# power.net
KiCad netlist of a schematic drawn in Altium Designer
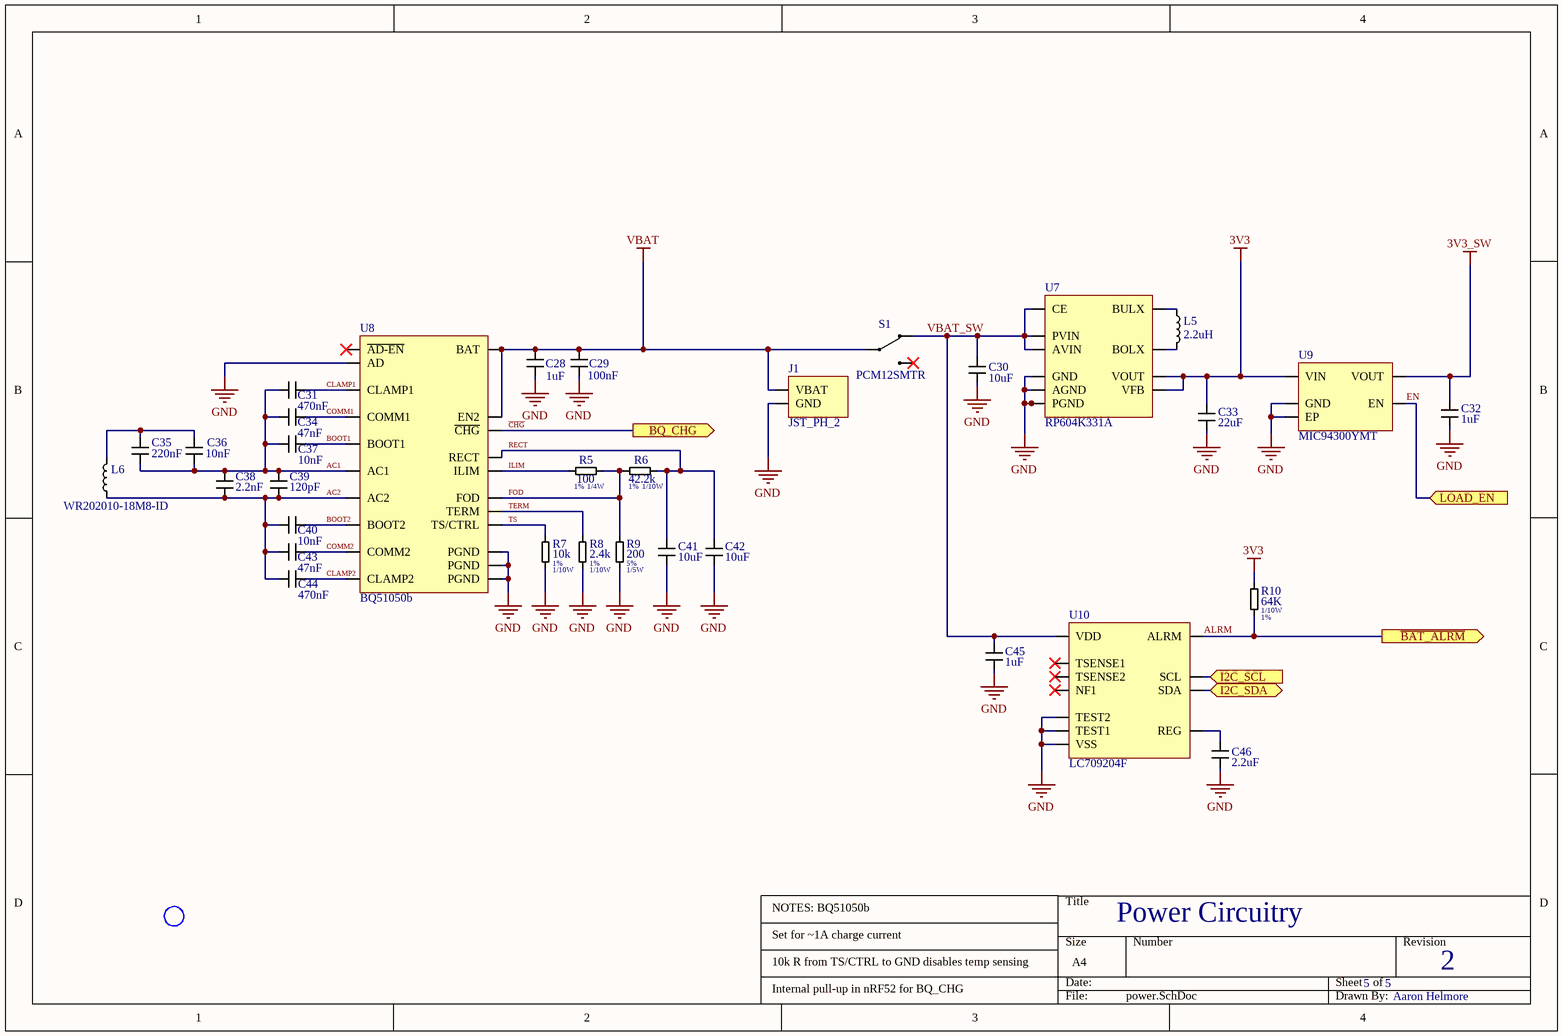
[diagram p0: power.SchDoc]

(export (version "E")
  (design (tool "Eeschema 10.0.6"))
  (components
    (comp (ref "C28")
      (value "1uF")
      (footprint "CAP_0402")
      (fields (field (name "VOLTAGE") "25V"))
      (libsource (lib "thesis_schem_lib") (part "Capacitor"))
    )
    (comp (ref "C29")
      (value "100nF")
      (footprint "CAP_0402")
      (fields (field (name "VOLTAGE") "25V"))
      (libsource (lib "thesis_schem_lib") (part "Capacitor"))
    )
    (comp (ref "C30")
      (value "10uF")
      (footprint "CAP_0603")
      (fields (field (name "VOLTAGE") "25V"))
      (libsource (lib "thesis_schem_lib") (part "Capacitor"))
    )
    (comp (ref "C31")
      (value "470nF")
      (footprint "CAP_0603")
      (fields (field (name "VOLTAGE") "25V"))
      (libsource (lib "thesis_schem_lib") (part "Capacitor"))
    )
    (comp (ref "C32")
      (value "1uF")
      (footprint "CAP_0402")
      (fields (field (name "VOLTAGE") "25V"))
      (libsource (lib "thesis_schem_lib") (part "Capacitor"))
    )
    (comp (ref "C33")
      (value "22uF")
      (footprint "CAP_0603")
      (fields (field (name "VOLTAGE") "10V"))
      (libsource (lib "thesis_schem_lib") (part "Capacitor"))
    )
    (comp (ref "C34")
      (value "47nF")
      (footprint "CAP_0402")
      (fields (field (name "VOLTAGE") "25V"))
      (libsource (lib "thesis_schem_lib") (part "Capacitor"))
    )
    (comp (ref "C35")
      (value "220nF")
      (footprint "CAP_0402")
      (fields (field (name "VOLTAGE") "25V"))
      (libsource (lib "thesis_schem_lib") (part "Capacitor"))
    )
    (comp (ref "C36")
      (value "10nF")
      (footprint "CAP_0402")
      (fields (field (name "VOLTAGE") "25V"))
      (libsource (lib "thesis_schem_lib") (part "Capacitor"))
    )
    (comp (ref "C37")
      (value "10nF")
      (footprint "CAP_0402")
      (fields (field (name "VOLTAGE") "25V"))
      (libsource (lib "") (part "Capacitor_1"))
    )
    (comp (ref "C38")
      (value "2.2nF")
      (footprint "CAP_0402")
      (fields (field (name "VOLTAGE") "50V"))
      (libsource (lib "thesis_schem_lib") (part "Capacitor"))
    )
    (comp (ref "C39")
      (value "120pF")
      (footprint "CAP_0402")
      (fields (field (name "VOLTAGE") "50V"))
      (libsource (lib "thesis_schem_lib") (part "Capacitor"))
    )
    (comp (ref "C40")
      (value "10nF")
      (footprint "CAP_0402")
      (fields (field (name "VOLTAGE") "25V"))
      (libsource (lib "thesis_schem_lib") (part "Capacitor"))
    )
    (comp (ref "C41")
      (value "10uF")
      (footprint "CAP_0603")
      (fields (field (name "VOLTAGE") "25V"))
      (libsource (lib "thesis_schem_lib") (part "Capacitor"))
    )
    (comp (ref "C42")
      (value "10uF")
      (footprint "CAP_0603")
      (fields (field (name "VOLTAGE") "25V"))
      (libsource (lib "thesis_schem_lib") (part "Capacitor"))
    )
    (comp (ref "C43")
      (value "47nF")
      (footprint "CAP_0402")
      (fields (field (name "VOLTAGE") "25V"))
      (libsource (lib "thesis_schem_lib") (part "Capacitor"))
    )
    (comp (ref "C44")
      (value "470nF")
      (footprint "CAP_0603")
      (fields (field (name "VOLTAGE") "25V"))
      (libsource (lib "thesis_schem_lib") (part "Capacitor"))
    )
    (comp (ref "C45")
      (value "1uF")
      (footprint "CAP_0402")
      (fields (field (name "VOLTAGE") "25V"))
      (libsource (lib "thesis_schem_lib") (part "Capacitor"))
    )
    (comp (ref "C46")
      (value "2.2uF")
      (footprint "CAP_0603")
      (fields (field (name "VOLTAGE") "25V"))
      (libsource (lib "thesis_schem_lib") (part "Capacitor"))
    )
    (comp (ref "J1")
      (value "JST_PH_2")
      (footprint "JST PH2 SMT")
      (description "JST PH series connector with 2 pins 1 row")
      (libsource (lib "thesis_schem_lib") (part "JST_PH_2"))
    )
    (comp (ref "L5")
      (value "2.2uH")
      (footprint "LQM2MPNxxxx")
      (libsource (lib "thesis_schem_lib") (part "Inductor"))
    )
    (comp (ref "L6")
      (value "WR202010-18M8-ID")
      (footprint "WR202010")
      (libsource (lib "thesis_schem_lib") (part "Inductor"))
    )
    (comp (ref "R5")
      (value "100")
      (footprint "RES_0402")
      (fields (field (name "TOLERANCE") "1%") (field (name "WATTAGE") "1/4W"))
      (libsource (lib "") (part "R_Small_1"))
    )
    (comp (ref "R6")
      (value "42.2k")
      (footprint "RES_0402")
      (fields (field (name "TOLERANCE") "1%") (field (name "WATTAGE") "1/10W"))
      (libsource (lib "") (part "R_Small_1"))
    )
    (comp (ref "R7")
      (value "10k")
      (footprint "RES_0402")
      (fields (field (name "TOLERANCE") "1%") (field (name "WATTAGE") "1/10W"))
      (libsource (lib "thesis_schem_lib") (part "R_Small"))
    )
    (comp (ref "R8")
      (value "2.4k")
      (footprint "RES_0402")
      (fields (field (name "TOLERANCE") "1%") (field (name "WATTAGE") "1/10W"))
      (libsource (lib "thesis_schem_lib") (part "R_Small"))
    )
    (comp (ref "R9")
      (value "200")
      (footprint "RES_0402")
      (fields (field (name "TOLERANCE") "5%") (field (name "WATTAGE") "1/5W"))
      (libsource (lib "thesis_schem_lib") (part "R_Small"))
    )
    (comp (ref "R10")
      (value "64K")
      (footprint "RES_0402")
      (fields (field (name "WATTAGE") "1/10W") (field (name "TOLERANCE") "1%"))
      (libsource (lib "thesis_schem_lib") (part "R_Small"))
    )
    (comp (ref "RXCOIL1")
      (value "RXCOIL_MISC")
      (footprint "RX_COIL_MISC")
      (libsource (lib "thesis_schem_lib") (part "RXCOIL_MISC"))
    )
    (comp (ref "S1")
      (value "PCM12SMTR")
      (footprint "PCM12SMTR")
      (description "CK Switches 300mA 6VDC SMT right-angle slide switch")
      (libsource (lib "thesis_schem_lib") (part "PCM12SMTR"))
    )
    (comp (ref "U7")
      (value "RP604K331A")
      (footprint "UDFN-12")
      (description "Nisshinbo Ultra-low quiescent current, 300mA, Buck-Boost DC/DC converter")
      (libsource (lib "thesis_schem_lib") (part "RP604K331A"))
    )
    (comp (ref "U8")
      (value "BQ51050b")
      (footprint "BQ51050b-VQFN")
      (description "Single stage wireless power receiver and Li-Ion/Li-Pol battery charger. Qi compatible")
      (libsource (lib "thesis_schem_lib") (part "BQ51050b"))
    )
    (comp (ref "U9")
      (value "MIC94300YMT")
      (footprint "MIC94300YMT")
      (description "200mA load switch")
      (libsource (lib "thesis_schem_lib") (part "MIC94300YMT"))
    )
    (comp (ref "U10")
      (value "LC709204F")
      (footprint "LC709204F")
      (description "onsemi I2C Li-Ion/Li-Poly Fuel Gauge")
      (libsource (lib "thesis_schem_lib") (part "LC709204F"))
    )
  )
  (nets
    (net (code "1") (name "/AC1") (class "Default")
      (node (ref "C31") (pin "2") (pinfunction "J11_2") (pintype "passive"))
      (node (ref "C34") (pin "2") (pinfunction "J11_2") (pintype "passive"))
      (node (ref "C35") (pin "1") (pinfunction "J12_1") (pintype "passive"))
      (node (ref "C36") (pin "1") (pinfunction "J12_1") (pintype "passive"))
      (node (ref "C37") (pin "1") (pinfunction "J12_1") (pintype "passive"))
      (node (ref "C38") (pin "2") (pinfunction "J11_2") (pintype "passive"))
      (node (ref "C39") (pin "2") (pinfunction "J11_2") (pintype "passive"))
      (node (ref "U8") (pin "2") (pinfunction "AC1_2") (pintype "passive"))
    )
    (net (code "2") (name "/AC2") (class "Default")
      (node (ref "C38") (pin "1") (pinfunction "J12_1") (pintype "passive"))
      (node (ref "C39") (pin "1") (pinfunction "J12_1") (pintype "passive"))
      (node (ref "C40") (pin "2") (pinfunction "J11_2") (pintype "passive"))
      (node (ref "C43") (pin "2") (pinfunction "J11_2") (pintype "passive"))
      (node (ref "C44") (pin "2") (pinfunction "J11_2") (pintype "passive"))
      (node (ref "L6") (pin "1") (pinfunction "1_1") (pintype "passive"))
      (node (ref "U8") (pin "19") (pinfunction "AC2_19") (pintype "passive"))
    )
    (net (code "3") (name "/ALRM") (class "Default")
      (node (ref "R10") (pin "2") (pinfunction "2_2") (pintype "passive"))
      (node (ref "U10") (pin "C1") (pinfunction "ALRM_C1") (pintype "passive"))
    )
    (net (code "4") (name "/BOOT1") (class "Default")
      (node (ref "C37") (pin "2") (pinfunction "J11_2") (pintype "passive"))
      (node (ref "U8") (pin "3") (pinfunction "BOOT1_3") (pintype "passive"))
    )
    (net (code "5") (name "/BOOT2") (class "Default")
      (node (ref "C40") (pin "1") (pinfunction "J12_1") (pintype "passive"))
      (node (ref "U8") (pin "17") (pinfunction "BOOT2_17") (pintype "passive"))
    )
    (net (code "6") (name "/CLAMP1") (class "Default")
      (node (ref "C31") (pin "1") (pinfunction "J12_1") (pintype "passive"))
      (node (ref "U8") (pin "5") (pinfunction "CLAMP1_5") (pintype "passive"))
    )
    (net (code "7") (name "/CLAMP2") (class "Default")
      (node (ref "C44") (pin "1") (pinfunction "J12_1") (pintype "passive"))
      (node (ref "U8") (pin "16") (pinfunction "CLAMP2_16") (pintype "passive"))
    )
    (net (code "8") (name "/COMM1") (class "Default")
      (node (ref "C34") (pin "1") (pinfunction "J12_1") (pintype "passive"))
      (node (ref "U8") (pin "6") (pinfunction "COMM1_6") (pintype "passive"))
    )
    (net (code "9") (name "/COMM2") (class "Default")
      (node (ref "C43") (pin "1") (pinfunction "J12_1") (pintype "passive"))
      (node (ref "U8") (pin "15") (pinfunction "COMM2_15") (pintype "passive"))
    )
    (net (code "10") (name "/EN") (class "Default")
      (node (ref "U9") (pin "1") (pinfunction "EN_1") (pintype "passive"))
    )
    (net (code "11") (name "/FOD") (class "Default")
      (node (ref "R5") (pin "2") (pinfunction "2_2") (pintype "passive"))
      (node (ref "R6") (pin "1") (pinfunction "1_1") (pintype "passive"))
      (node (ref "R9") (pin "1") (pinfunction "1_1") (pintype "passive"))
      (node (ref "U8") (pin "14") (pinfunction "FOD_14") (pintype "passive"))
    )
    (net (code "12") (name "/I2C_SCL") (class "Default")
      (node (ref "U10") (pin "A1") (pinfunction "SCL_A1") (pintype "passive"))
    )
    (net (code "13") (name "/I2C_SDA") (class "Default")
      (node (ref "U10") (pin "B1") (pinfunction "SDA_B1") (pintype "passive"))
    )
    (net (code "14") (name "/ILIM") (class "Default")
      (node (ref "R5") (pin "1") (pinfunction "1_1") (pintype "passive"))
      (node (ref "U8") (pin "12") (pinfunction "ILIM_12") (pintype "passive"))
    )
    (net (code "15") (name "/RECT") (class "Default")
      (node (ref "C41") (pin "2") (pinfunction "J11_2") (pintype "passive"))
      (node (ref "C42") (pin "2") (pinfunction "J11_2") (pintype "passive"))
      (node (ref "R6") (pin "2") (pinfunction "2_2") (pintype "passive"))
      (node (ref "U8") (pin "18") (pinfunction "RECT_18") (pintype "passive"))
    )
    (net (code "16") (name "/TERM") (class "Default")
      (node (ref "R8") (pin "1") (pinfunction "1_1") (pintype "passive"))
      (node (ref "U8") (pin "10") (pinfunction "TERM_10") (pintype "passive"))
    )
    (net (code "17") (name "/TS") (class "Default")
      (node (ref "R7") (pin "1") (pinfunction "1_1") (pintype "passive"))
      (node (ref "U8") (pin "13") (pinfunction "TS/CTRL_13") (pintype "passive"))
    )
    (net (code "18") (name "/VBAT_SW") (class "Default")
      (node (ref "C30") (pin "2") (pinfunction "J11_2") (pintype "passive"))
      (node (ref "C45") (pin "2") (pinfunction "J11_2") (pintype "passive"))
      (node (ref "S1") (pin "1") (pinfunction "1_1") (pintype "passive"))
      (node (ref "U10") (pin "A4") (pinfunction "VDD_A4") (pintype "passive"))
      (node (ref "U7") (pin "1") (pinfunction "AVIN_1") (pintype "passive"))
      (node (ref "U7") (pin "12") (pinfunction "PVIN_12") (pintype "passive"))
      (node (ref "U7") (pin "2") (pinfunction "CE_2") (pintype "passive"))
    )
    (net (code "19") (name "/~{CHG}") (class "Default")
      (node (ref "U8") (pin "7") (pinfunction "~{CHG}_7") (pintype "passive"))
    )
    (net (code "20") (name "3V3") (class "Default")
      (node (ref "C33") (pin "2") (pinfunction "J11_2") (pintype "passive"))
      (node (ref "R10") (pin "1") (pinfunction "1_1") (pintype "passive"))
      (node (ref "U7") (pin "6") (pinfunction "VFB_6") (pintype "passive"))
      (node (ref "U7") (pin "7") (pinfunction "VOUT_7") (pintype "passive"))
      (node (ref "U9") (pin "4") (pinfunction "VIN_4") (pintype "passive"))
    )
    (net (code "21") (name "3V3_SW") (class "Default")
      (node (ref "C32") (pin "2") (pinfunction "J11_2") (pintype "passive"))
      (node (ref "U9") (pin "3") (pinfunction "VOUT_3") (pintype "passive"))
    )
    (net (code "22") (name "GND") (class "Default")
      (node (ref "C28") (pin "1") (pinfunction "J12_1") (pintype "passive"))
      (node (ref "C29") (pin "1") (pinfunction "J12_1") (pintype "passive"))
      (node (ref "C30") (pin "1") (pinfunction "J12_1") (pintype "passive"))
      (node (ref "C32") (pin "1") (pinfunction "J12_1") (pintype "passive"))
      (node (ref "C33") (pin "1") (pinfunction "J12_1") (pintype "passive"))
      (node (ref "C41") (pin "1") (pinfunction "J12_1") (pintype "passive"))
      (node (ref "C42") (pin "1") (pinfunction "J12_1") (pintype "passive"))
      (node (ref "C45") (pin "1") (pinfunction "J12_1") (pintype "passive"))
      (node (ref "C46") (pin "1") (pinfunction "J12_1") (pintype "passive"))
      (node (ref "J1") (pin "2") (pinfunction "GND_2") (pintype "passive"))
      (node (ref "R7") (pin "2") (pinfunction "2_2") (pintype "passive"))
      (node (ref "R8") (pin "2") (pinfunction "2_2") (pintype "passive"))
      (node (ref "R9") (pin "2") (pinfunction "2_2") (pintype "passive"))
      (node (ref "U10") (pin "A2") (pinfunction "VSS_A2") (pintype "passive"))
      (node (ref "U10") (pin "B2") (pinfunction "TEST2_B2") (pintype "passive"))
      (node (ref "U10") (pin "C2") (pinfunction "TEST1_C2") (pintype "passive"))
      (node (ref "U7") (pin "10") (pinfunction "PGND_10") (pintype "passive"))
      (node (ref "U7") (pin "13") (pinfunction "GND_13") (pintype "passive"))
      (node (ref "U7") (pin "3") (pinfunction "PGND_3") (pintype "passive"))
      (node (ref "U7") (pin "4") (pinfunction "PGND_4") (pintype "passive"))
      (node (ref "U7") (pin "5") (pinfunction "AGND_5") (pintype "passive"))
      (node (ref "U7") (pin "9") (pinfunction "PGND_9") (pintype "passive"))
      (node (ref "U8") (pin "0") (pinfunction "PGND_0") (pintype "passive"))
      (node (ref "U8") (pin "1") (pinfunction "PGND_1") (pintype "passive"))
      (node (ref "U8") (pin "20") (pinfunction "PGND_20") (pintype "passive"))
      (node (ref "U8") (pin "9") (pinfunction "AD_9") (pintype "passive"))
      (node (ref "U9") (pin "2") (pinfunction "GND_2") (pintype "passive"))
      (node (ref "U9") (pin "EP1") (pinfunction "EP_EP1") (pintype "passive"))
    )
    (net (code "23") (name "Net-(C35-J11)") (class "Default")
      (node (ref "C35") (pin "2") (pinfunction "J11_2") (pintype "passive"))
      (node (ref "C36") (pin "2") (pinfunction "J11_2") (pintype "passive"))
      (node (ref "L6") (pin "2") (pinfunction "2_2") (pintype "passive"))
    )
    (net (code "24") (name "Net-(C46-J11)") (class "Default")
      (node (ref "C46") (pin "2") (pinfunction "J11_2") (pintype "passive"))
      (node (ref "U10") (pin "A3") (pinfunction "REG_A3") (pintype "passive"))
    )
    (net (code "25") (name "Net-(U7-BOLX)") (class "Default")
      (node (ref "L5") (pin "2") (pinfunction "2_2") (pintype "passive"))
      (node (ref "U7") (pin "8") (pinfunction "BOLX_8") (pintype "passive"))
    )
    (net (code "26") (name "Net-(U7-BULX)") (class "Default")
      (node (ref "L5") (pin "1") (pinfunction "1_1") (pintype "passive"))
      (node (ref "U7") (pin "11") (pinfunction "BULX_11") (pintype "passive"))
    )
    (net (code "27") (name "VBAT") (class "Default")
      (node (ref "C28") (pin "2") (pinfunction "J11_2") (pintype "passive"))
      (node (ref "C29") (pin "2") (pinfunction "J11_2") (pintype "passive"))
      (node (ref "J1") (pin "1") (pinfunction "VBAT_1") (pintype "passive"))
      (node (ref "S1") (pin "2") (pinfunction "2_2") (pintype "passive"))
      (node (ref "U8") (pin "11") (pinfunction "EN2_11") (pintype "passive"))
      (node (ref "U8") (pin "4") (pinfunction "BAT_4") (pintype "passive"))
    )
    (net (code "28") (name "unconnected-(S1-Pad3)") (class "Default")
      (node (ref "S1") (pin "3") (pinfunction "3_3") (pintype "passive+no_connect"))
    )
    (net (code "29") (name "unconnected-(U8-~{AD-EN}-Pad8)") (class "Default")
      (node (ref "U8") (pin "8") (pinfunction "~{AD-EN}_8") (pintype "passive+no_connect"))
    )
    (net (code "30") (name "unconnected-(U10-NF1-PadC3)") (class "Default")
      (node (ref "U10") (pin "C3") (pinfunction "NF1_C3") (pintype "passive+no_connect"))
    )
    (net (code "31") (name "unconnected-(U10-TSENSE1-PadB4)") (class "Default")
      (node (ref "U10") (pin "B4") (pinfunction "TSENSE1_B4") (pintype "passive+no_connect"))
    )
    (net (code "32") (name "unconnected-(U10-TSENSE2-PadB3)") (class "Default")
      (node (ref "U10") (pin "B3") (pinfunction "TSENSE2_B3") (pintype "passive+no_connect"))
    )
  )
)
